# Ledtourch.net
KiCad netlist of a schematic drawn in Altium Designer
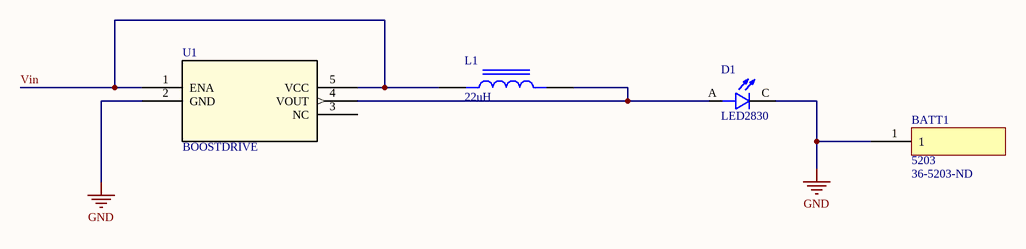
[diagram p0: Ledtourch.SchDoc]

(export (version "E")
  (design (tool "Eeschema 10.0.6"))
  (components
    (comp (ref "BATT1")
      (value "5203")
      (footprint "AAA_BATT_SPRING_SOL")
      (description "3M Half Facepiece Disposable Respirator Assembly 5203, OrganicVapor/Acid Gas")
      (fields
        (field (name "MANUFACTURER") "Keystone Electronics")
        (field (name "SUPPLIER PART NUMBER 1") "36-5203-ND")
      )
      (libsource (lib "Ledtourch") (part "5203"))
    )
    (comp (ref "D1")
      (value "LED2830")
      (footprint "LED_OF-SMD2835Y")
      (description "LED Uni-Color White 127lm 4000K Chip LED 2-Pin SMD T/R")
      (fields
        (field (name "MANUFACTURER") "Bridgelux")
        (field (name "MANUFACTURER PART NUMBER") "BXEN-40E-13H-9B-00-0-0")
      )
      (libsource (lib "Ledtourch") (part "BXEN-40E-13H-9B-00-0-0"))
    )
    (comp (ref "L1")
      (value "22uH")
      (footprint "IND_ASPI-0315S-220M-T")
      (description "Inductor Power Shielded Wirewound 22uH 20% 100KHz 400mA 430mOhm DCR T/R")
      (fields
        (field (name "MANUFACTURER") "Abracon")
        (field (name "MANUFACTURER PART NUMBER") "ASPI-0315S-220M-T")
      )
      (libsource (lib "Ledtourch") (part "ASPI-0315S-220M-T"))
    )
    (comp (ref "U1")
      (value "BOOSTDRIVE")
      (footprint "TSOT23-5_ZXLD383_DIO")
      (description "ZXLD383 Series 50 mA 330 kHz Single or Multi Cell LED Driver Solution TSOT-23-5")
      (fields
        (field (name "MANUFACTURER") "Diodes Zetex")
        (field (name "MANUFACTURER PART NUMBER") "ZXLD383ET5TA")
      )
      (libsource (lib "Ledtourch") (part "ZXLD383ET5TA"))
    )
  )
  (nets
    (net (code "1") (name "/Vin") (class "Default")
      (node (ref "L1") (pin "1") (pinfunction "1_1") (pintype "passive"))
      (node (ref "U1") (pin "1") (pinfunction "ENA_1") (pintype "passive"))
      (node (ref "U1") (pin "5") (pinfunction "VCC_5") (pintype "power_in"))
    )
    (net (code "2") (name "GND") (class "Default")
      (node (ref "BATT1") (pin "1") (pinfunction "1_1") (pintype "passive"))
      (node (ref "D1") (pin "C") (pinfunction "C_C") (pintype "passive"))
      (node (ref "U1") (pin "2") (pinfunction "GND_2") (pintype "power_in"))
    )
    (net (code "3") (name "Net-(U1-VOUT)") (class "Default")
      (node (ref "D1") (pin "A") (pinfunction "A_A") (pintype "passive"))
      (node (ref "L1") (pin "2") (pinfunction "2_2") (pintype "passive"))
      (node (ref "U1") (pin "4") (pinfunction "VOUT_4") (pintype "output"))
    )
    (net (code "4") (name "unconnected-(U1-NC-Pad3)") (class "Default")
      (node (ref "U1") (pin "3") (pinfunction "NC_3") (pintype "passive"))
    )
  )
)
